# Output_Connectors.net
KiCad netlist of a schematic drawn in Altium Designer
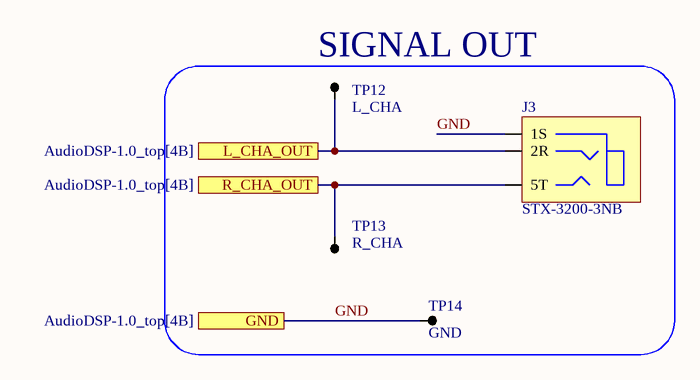
[diagram p0: Output_Connectors.SchDoc]

(export (version "E")
  (design (tool "Eeschema 10.0.6"))
  (components
    (comp (ref "J3")
      (value "STX-3200-3NB")
      (footprint "JACK-3.5-3POS")
      (libsource (lib "LIB2022 - Connectors") (part "STX-3200-3NB"))
    )
    (comp (ref "TP12")
      (value "L_CHA")
      (footprint "534-5280")
      (libsource (lib "LIB2022 - Mechanicals") (part "TP-CLAW"))
    )
    (comp (ref "TP13")
      (value "R_CHA")
      (footprint "534-5280")
      (libsource (lib "LIB2022 - Mechanicals") (part "TP-CLAW"))
    )
    (comp (ref "TP14")
      (value "GND")
      (footprint "534-5280")
      (libsource (lib "LIB2022 - Mechanicals") (part "TP-CLAW"))
    )
  )
  (nets
    (net (code "1") (name "/GND") (class "Default")
      (node (ref "J3") (pin "1S") (pinfunction "1S_1S") (pintype "passive"))
      (node (ref "TP14") (pin "1") (pinfunction "1_1") (pintype "passive"))
    )
    (net (code "2") (name "/L_CHA_OUT") (class "Default")
      (node (ref "J3") (pin "2R") (pinfunction "2R_2R") (pintype "passive"))
      (node (ref "TP12") (pin "1") (pinfunction "1_1") (pintype "passive"))
    )
    (net (code "3") (name "/R_CHA_OUT") (class "Default")
      (node (ref "J3") (pin "5T") (pinfunction "5T_5T") (pintype "passive"))
      (node (ref "TP13") (pin "1") (pinfunction "1_1") (pintype "passive"))
    )
  )
)
